# SCH_Nucleo__LCD__v3_2022-11-11.net
KiCad netlist of a schematic drawn in EasyEDA
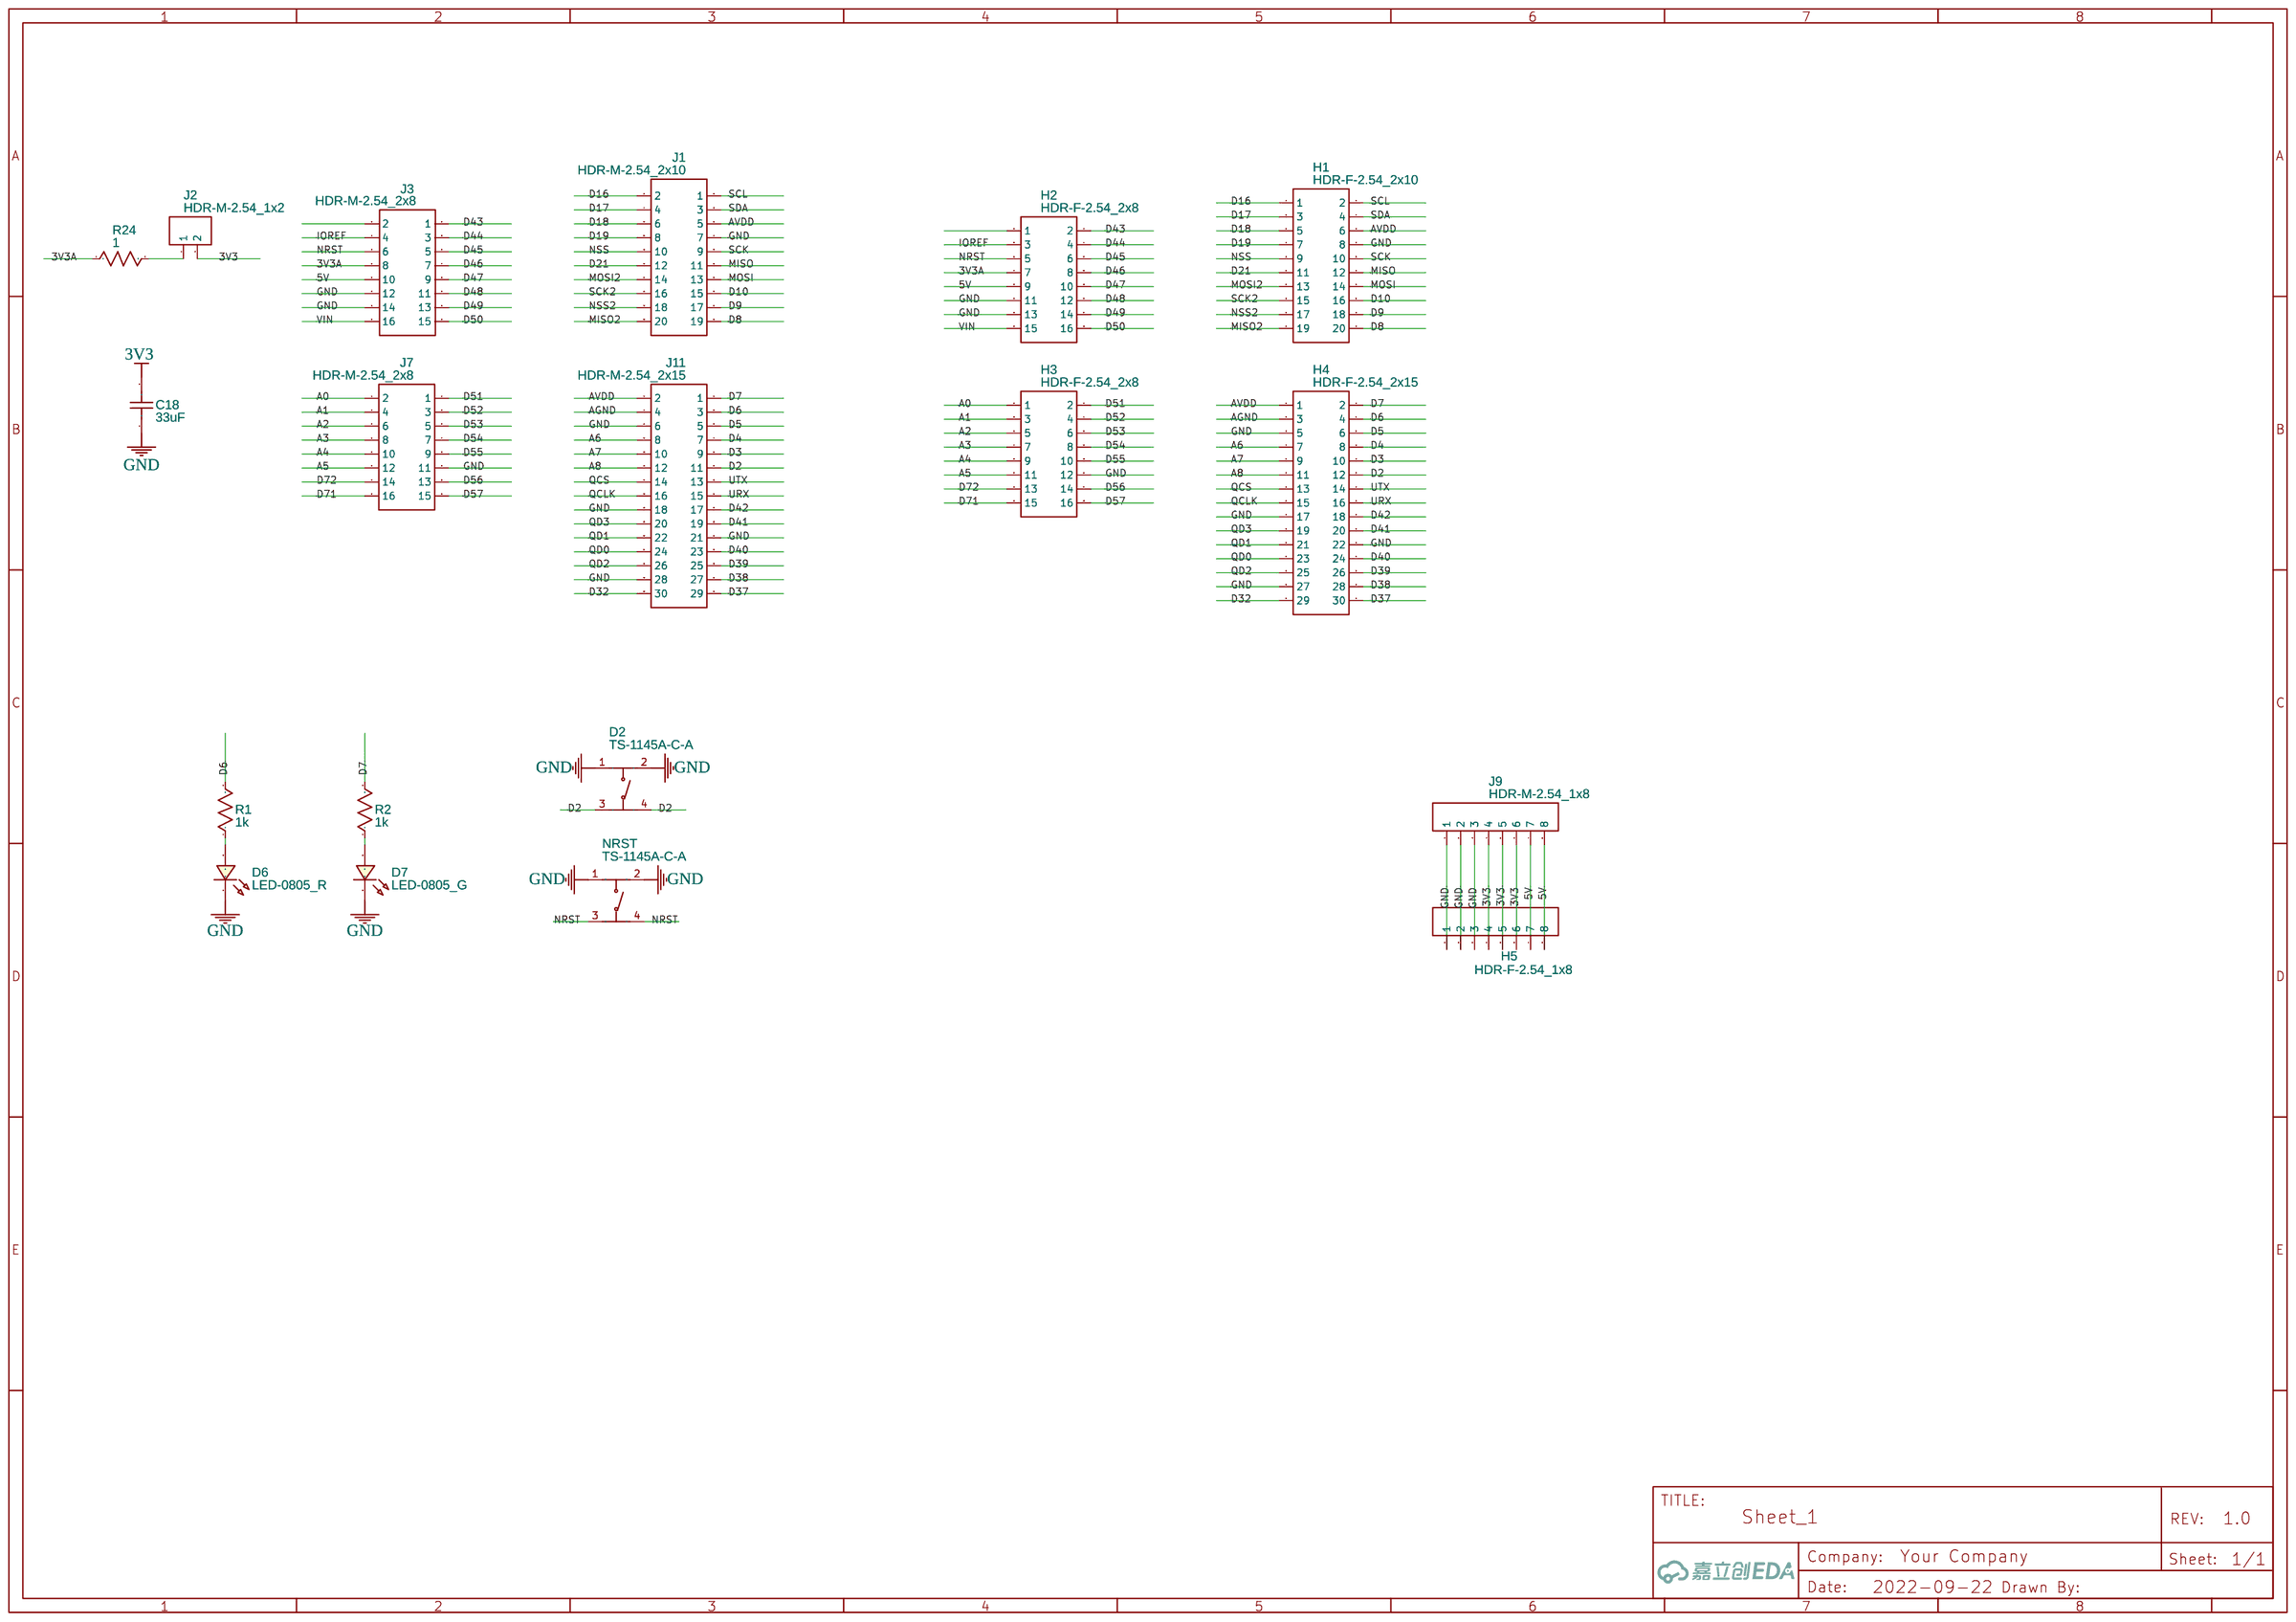
[diagram p0: 连接器]
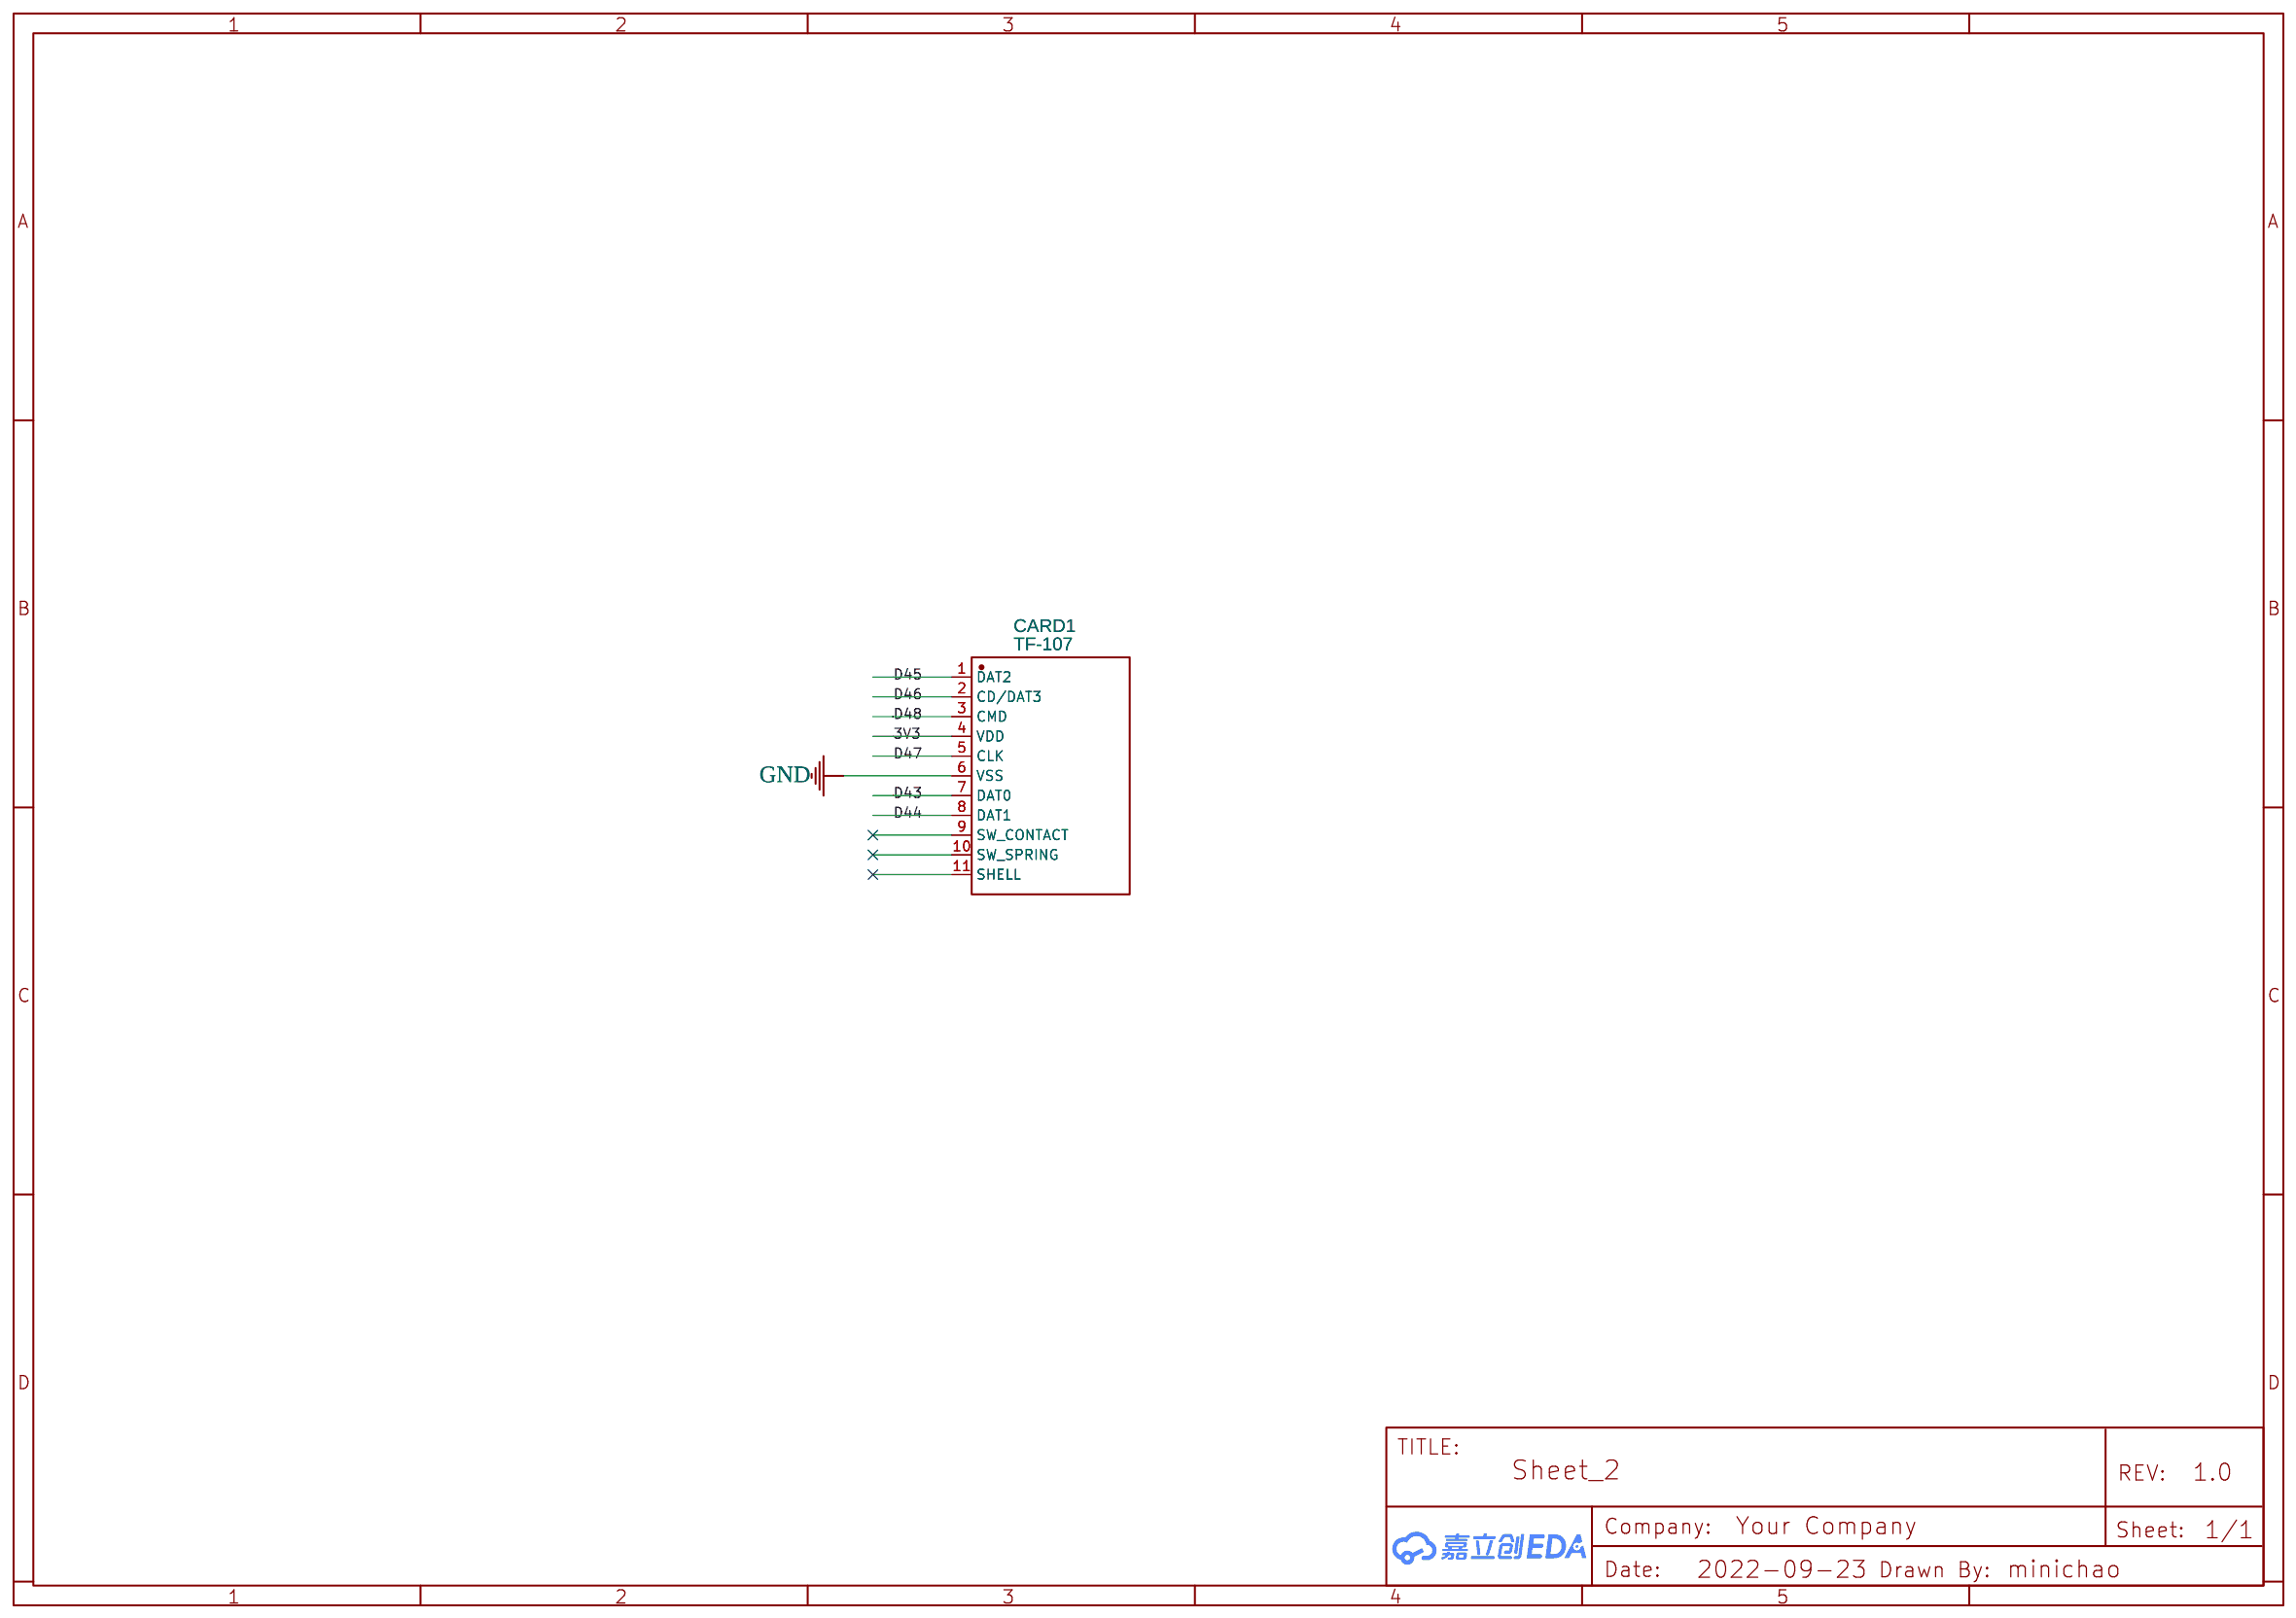
[diagram p1: 存储]
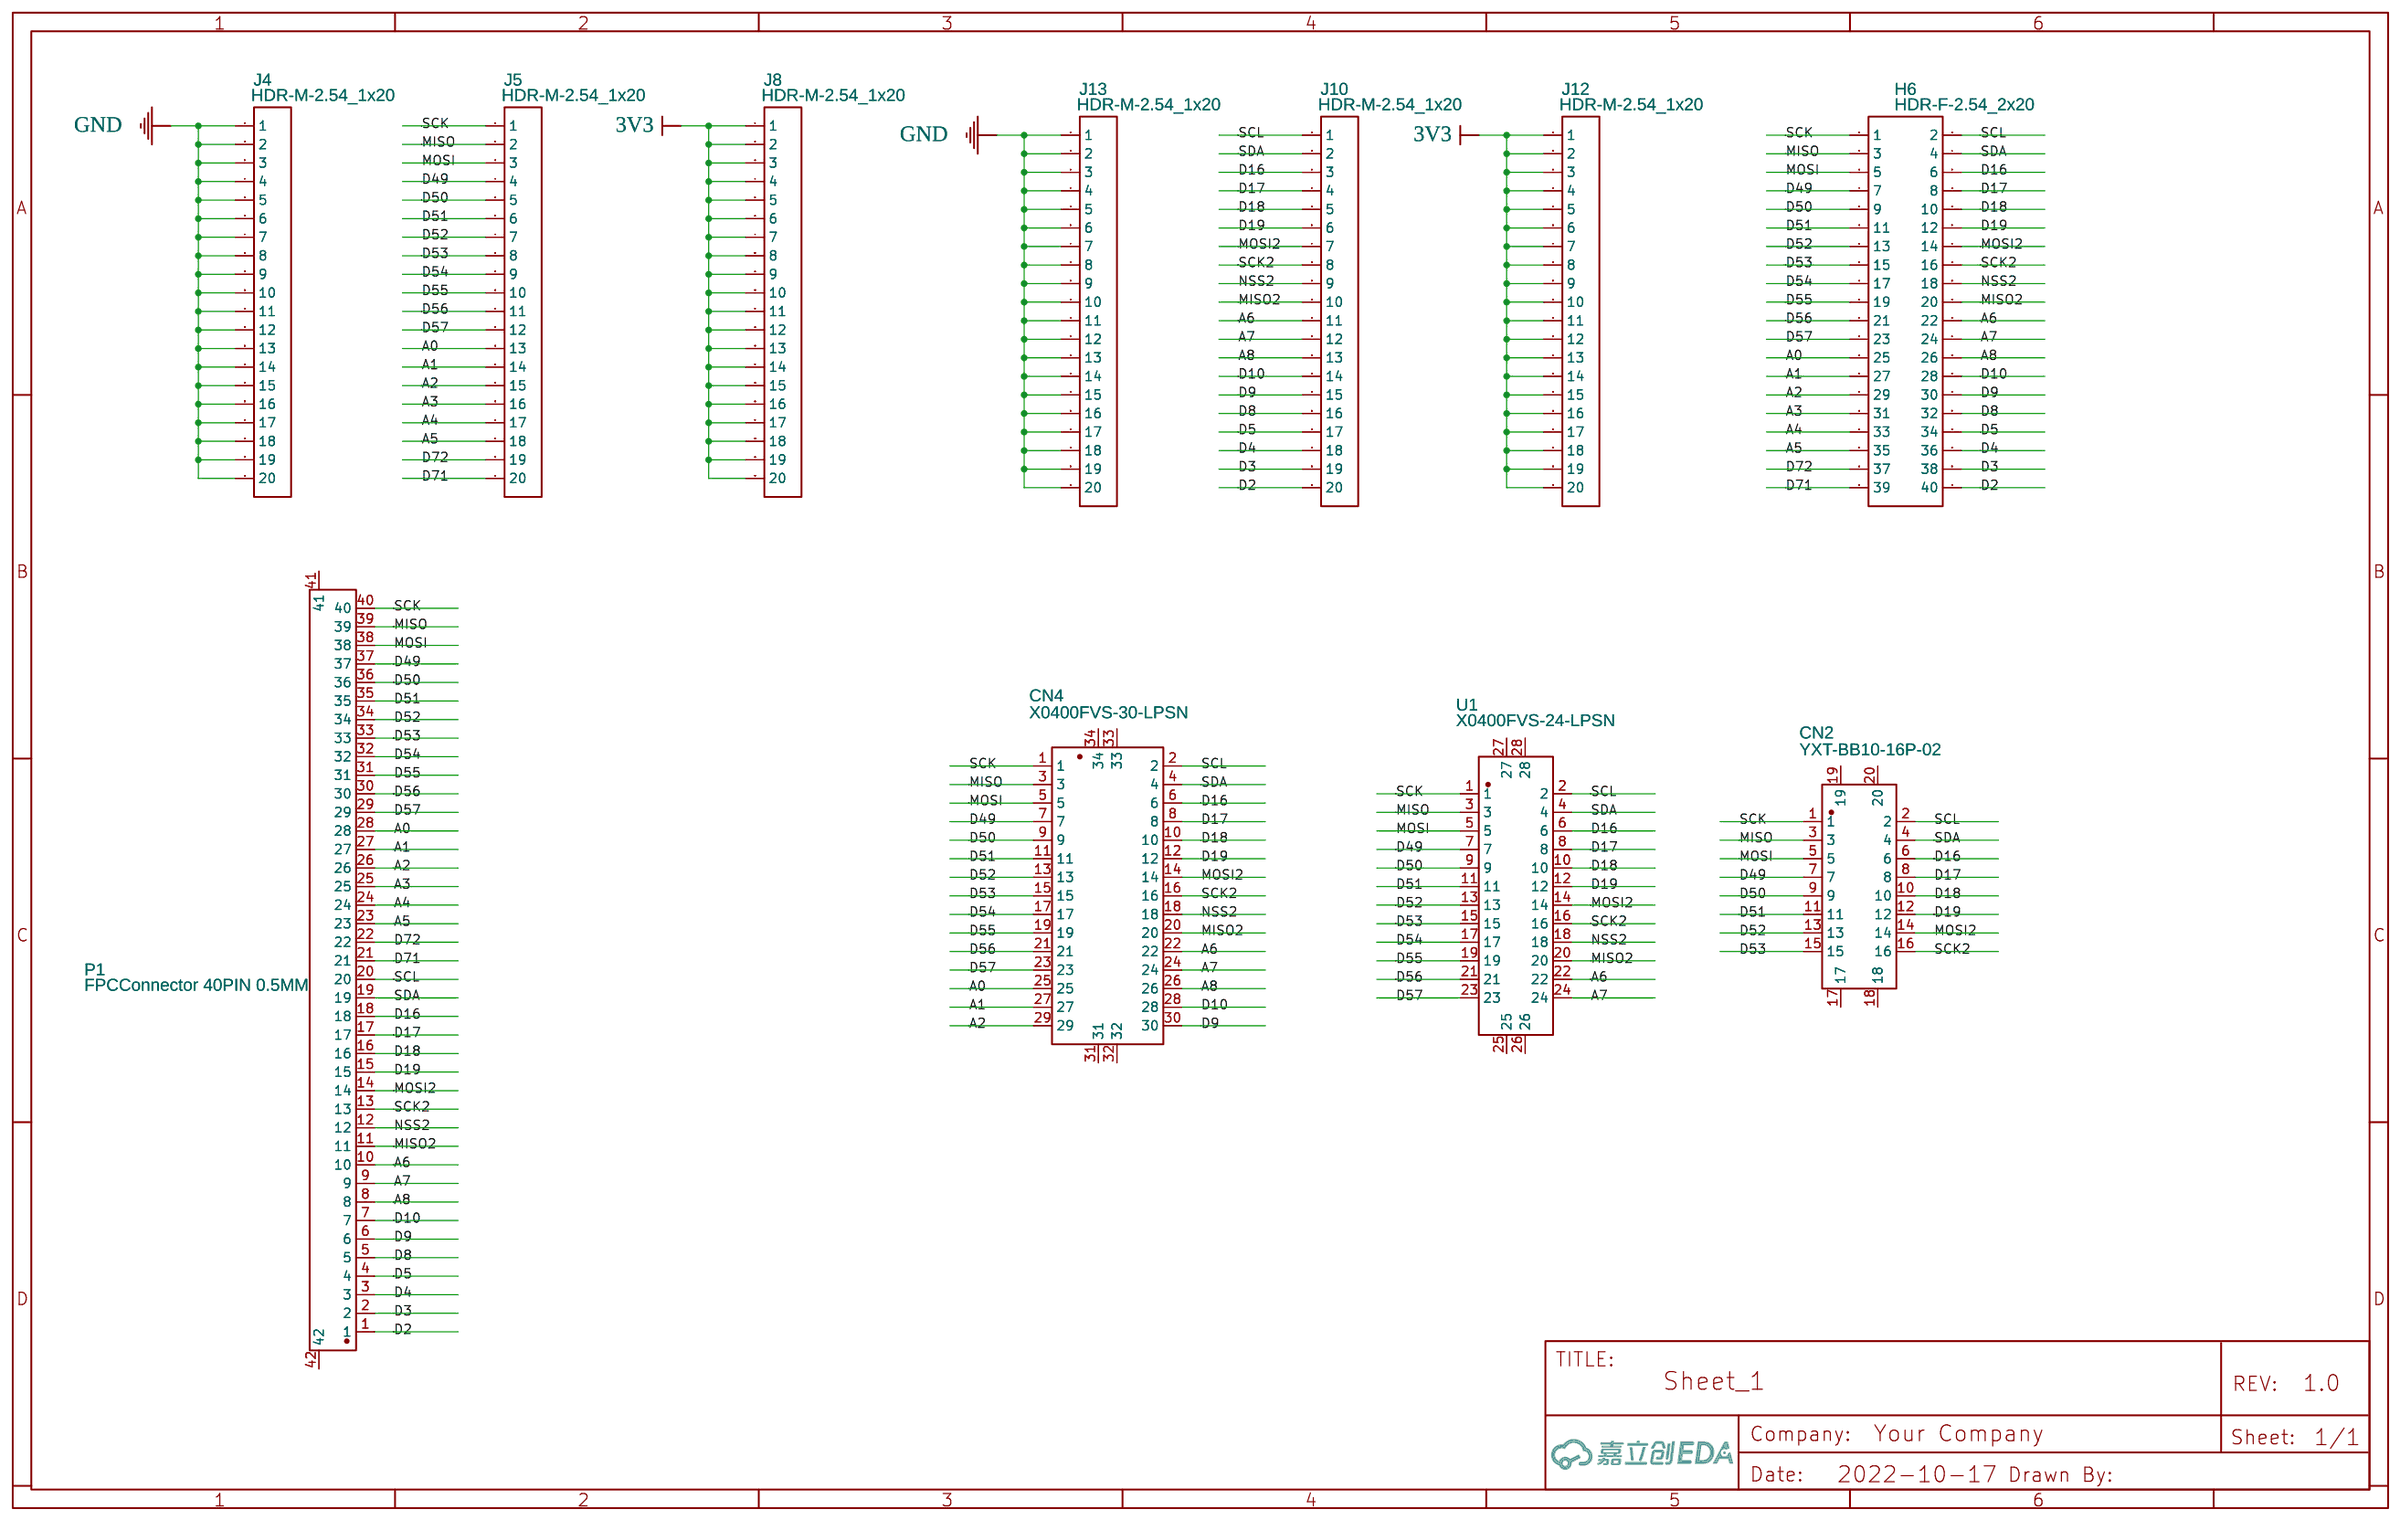
[diagram p2: 显示]

(export (version "E")
  (design (tool "Eeschema 10.0.6"))
  (components
    (comp (ref "C18")
      (value "33uF")
      (fields
        (field (name "BOM_Manufacturer Part") "C3225X5R0J336MT0A0N")
        (field (name "BOM_Supplier Part") "C695362")
      )
      (libsource (lib "") (part "C3225X5R0J336MT0A0N"))
    )
    (comp (ref "D2")
      (value "TS-1145A-C-A")
      (fields (field (name "BOM_Supplier Part") "C318903"))
      (libsource (lib "") (part "TS-1145A-C-A"))
    )
    (comp (ref "D6")
      (value "LED-0805_R")
      (fields
        (field (name "BOM_Manufacturer Part") "17-21SURC/S530-A3/TR8")
        (field (name "BOM_Supplier Part") "C72037")
      )
      (libsource (lib "") (part "LED-0805_R"))
    )
    (comp (ref "D7")
      (value "LED-0805_G")
      (fields (field (name "BOM_Manufacturer Part") "NCD0805G1") (field (name "BOM_Supplier Part") "C84260"))
      (libsource (lib "") (part "LED-0805_G"))
    )
    (comp (ref "H1")
      (value "HDR-F-2.54_2x10")
      (fields (field (name "BOM_Supplier Part") "C30867"))
      (libsource (lib "") (part "HDR-F-2.54_2x10"))
    )
    (comp (ref "H2")
      (value "HDR-F-2.54_2x8")
      (fields (field (name "BOM_Supplier Part") "C30734"))
      (libsource (lib "") (part "HDR-F-2.54_2x8"))
    )
    (comp (ref "H3")
      (value "HDR-F-2.54_2x8")
      (fields (field (name "BOM_Supplier Part") "C30734"))
      (libsource (lib "") (part "HDR-F-2.54_2x8"))
    )
    (comp (ref "H4")
      (value "HDR-F-2.54_2x15")
      (fields (field (name "BOM_Supplier Part") "C169818"))
      (libsource (lib "") (part "HDR-F-2.54_2x15"))
    )
    (comp (ref "H5")
      (value "HDR-F-2.54_1x8")
      (fields (field (name "BOM_Supplier Part") "C225505"))
      (libsource (lib "") (part "HDR-F-2.54_1x8"))
    )
    (comp (ref "J1")
      (value "HDR-M-2.54_2x10")
      (fields (field (name "BOM_Supplier Part") "C124359"))
      (libsource (lib "") (part "HDR-M-2.54_2x10"))
    )
    (comp (ref "J2")
      (value "HDR-M-2.54_1x2")
      (fields (field (name "BOM_Supplier Part") "C124375"))
      (libsource (lib "") (part "HDR-M-2.54_1x2"))
    )
    (comp (ref "J3")
      (value "HDR-M-2.54_2x8")
      (fields (field (name "BOM_Supplier Part") "C68234"))
      (libsource (lib "") (part "HDR-M-2.54_2x8"))
    )
    (comp (ref "J7")
      (value "HDR-M-2.54_2x8")
      (fields (field (name "BOM_Supplier Part") "C68234"))
      (libsource (lib "") (part "HDR-M-2.54_2x8_1"))
    )
    (comp (ref "J9")
      (value "HDR-M-2.54_1x8")
      (fields (field (name "BOM_Supplier Part") "C190820"))
      (libsource (lib "") (part "HDR-M-2.54_1x8"))
    )
    (comp (ref "J11")
      (value "HDR-M-2.54_2x15")
      (fields (field (name "BOM_Supplier Part") "C56496"))
      (libsource (lib "") (part "HDR-M-2.54_2x15"))
    )
    (comp (ref "NRST")
      (value "TS-1145A-C-A")
      (fields (field (name "BOM_Supplier Part") "C318903"))
      (libsource (lib "") (part "TS-1145A-C-A_1"))
    )
    (comp (ref "R1")
      (value "1k")
      (fields
        (field (name "BOM_Manufacturer Part") "TC0525F1001T5E")
        (field (name "BOM_Supplier Part") "C75781")
      )
      (libsource (lib "") (part "R_0805_US"))
    )
    (comp (ref "R2")
      (value "1k")
      (fields
        (field (name "BOM_Manufacturer Part") "TC0525F1001T5E")
        (field (name "BOM_Supplier Part") "C75781")
      )
      (libsource (lib "") (part "R_0805_US"))
    )
    (comp (ref "R24") (value "1") (libsource (lib "") (part "R_0805_US_1")))
    (comp (ref "CARD1")
      (value "TF-107")
      (fields (field (name "BOM_Supplier Part") "C266615"))
      (libsource (lib "") (part "TF-107"))
    )
    (comp (ref "CN2")
      (value "YXT-BB10-16P-02")
      (fields (field (name "BOM_Supplier Part") "C2763972"))
      (libsource (lib "") (part "YXT-BB10-16P-02"))
    )
    (comp (ref "CN4")
      (value "X0400FVS-30-LPSN")
      (fields (field (name "BOM_Supplier Part") "C2880693"))
      (libsource (lib "") (part "X0400FVS-30-LPSN"))
    )
    (comp (ref "H6")
      (value "HDR-F-2.54_2x20")
      (fields (field (name "BOM_Supplier Part") "C50982"))
      (libsource (lib "") (part "HDR-F-2.54_2x20"))
    )
    (comp (ref "J4")
      (value "HDR-M-2.54_1x20")
      (fields (field (name "BOM_Supplier Part") "C50981"))
      (libsource (lib "") (part "HDR-M-2.54_1x20"))
    )
    (comp (ref "J5")
      (value "HDR-M-2.54_1x20")
      (fields (field (name "BOM_Supplier Part") "C50981"))
      (libsource (lib "") (part "HDR-M-2.54_1x20"))
    )
    (comp (ref "J8")
      (value "HDR-M-2.54_1x20")
      (fields (field (name "BOM_Supplier Part") "C50981"))
      (libsource (lib "") (part "HDR-M-2.54_1x20"))
    )
    (comp (ref "J10")
      (value "HDR-M-2.54_1x20")
      (fields (field (name "BOM_Supplier Part") "C50981"))
      (libsource (lib "") (part "HDR-M-2.54_1x20"))
    )
    (comp (ref "J12")
      (value "HDR-M-2.54_1x20")
      (fields (field (name "BOM_Supplier Part") "C50981"))
      (libsource (lib "") (part "HDR-M-2.54_1x20"))
    )
    (comp (ref "J13")
      (value "HDR-M-2.54_1x20")
      (fields (field (name "BOM_Supplier Part") "C50981"))
      (libsource (lib "") (part "HDR-M-2.54_1x20"))
    )
    (comp (ref "P1")
      (value "FPCConnector 40PIN 0.5MM")
      (fields (field (name "BOM_Manufacturer Part") "0.5-40P翻盖") (field (name "BOM_Supplier Part") "C9160"))
      (libsource (lib "") (part "FPCConnector 40PIN 0.5MM"))
    )
    (comp (ref "U1")
      (value "X0400FVS-24-LPSN")
      (fields (field (name "BOM_Supplier Part") "C2880692"))
      (libsource (lib "") (part "X0400FVS-24-LPSN"))
    )
  )
  (nets
    (net (code "1") (name "3V3") (class "Default")
      (node (ref "C18") (pin "2") (pinfunction "2_2") (pintype "unspecified"))
      (node (ref "CARD1") (pin "4") (pinfunction "VDD_4") (pintype "unspecified"))
      (node (ref "H5") (pin "4") (pinfunction "4_4") (pintype "unspecified"))
      (node (ref "H5") (pin "5") (pinfunction "5_5") (pintype "unspecified"))
      (node (ref "H5") (pin "6") (pinfunction "6_6") (pintype "unspecified"))
      (node (ref "J12") (pin "1") (pinfunction "1_1") (pintype "unspecified"))
      (node (ref "J12") (pin "10") (pinfunction "10_10") (pintype "unspecified"))
      (node (ref "J12") (pin "11") (pinfunction "11_11") (pintype "unspecified"))
      (node (ref "J12") (pin "12") (pinfunction "12_12") (pintype "unspecified"))
      (node (ref "J12") (pin "13") (pinfunction "13_13") (pintype "unspecified"))
      (node (ref "J12") (pin "14") (pinfunction "14_14") (pintype "unspecified"))
      (node (ref "J12") (pin "15") (pinfunction "15_15") (pintype "unspecified"))
      (node (ref "J12") (pin "16") (pinfunction "16_16") (pintype "unspecified"))
      (node (ref "J12") (pin "17") (pinfunction "17_17") (pintype "unspecified"))
      (node (ref "J12") (pin "18") (pinfunction "18_18") (pintype "unspecified"))
      (node (ref "J12") (pin "19") (pinfunction "19_19") (pintype "unspecified"))
      (node (ref "J12") (pin "2") (pinfunction "2_2") (pintype "unspecified"))
      (node (ref "J12") (pin "20") (pinfunction "20_20") (pintype "unspecified"))
      (node (ref "J12") (pin "3") (pinfunction "3_3") (pintype "unspecified"))
      (node (ref "J12") (pin "4") (pinfunction "4_4") (pintype "unspecified"))
      (node (ref "J12") (pin "5") (pinfunction "5_5") (pintype "unspecified"))
      (node (ref "J12") (pin "6") (pinfunction "6_6") (pintype "unspecified"))
      (node (ref "J12") (pin "7") (pinfunction "7_7") (pintype "unspecified"))
      (node (ref "J12") (pin "8") (pinfunction "8_8") (pintype "unspecified"))
      (node (ref "J12") (pin "9") (pinfunction "9_9") (pintype "unspecified"))
      (node (ref "J2") (pin "2") (pinfunction "2_2") (pintype "unspecified"))
      (node (ref "J8") (pin "1") (pinfunction "1_1") (pintype "unspecified"))
      (node (ref "J8") (pin "10") (pinfunction "10_10") (pintype "unspecified"))
      (node (ref "J8") (pin "11") (pinfunction "11_11") (pintype "unspecified"))
      (node (ref "J8") (pin "12") (pinfunction "12_12") (pintype "unspecified"))
      (node (ref "J8") (pin "13") (pinfunction "13_13") (pintype "unspecified"))
      (node (ref "J8") (pin "14") (pinfunction "14_14") (pintype "unspecified"))
      (node (ref "J8") (pin "15") (pinfunction "15_15") (pintype "unspecified"))
      (node (ref "J8") (pin "16") (pinfunction "16_16") (pintype "unspecified"))
      (node (ref "J8") (pin "17") (pinfunction "17_17") (pintype "unspecified"))
      (node (ref "J8") (pin "18") (pinfunction "18_18") (pintype "unspecified"))
      (node (ref "J8") (pin "19") (pinfunction "19_19") (pintype "unspecified"))
      (node (ref "J8") (pin "2") (pinfunction "2_2") (pintype "unspecified"))
      (node (ref "J8") (pin "20") (pinfunction "20_20") (pintype "unspecified"))
      (node (ref "J8") (pin "3") (pinfunction "3_3") (pintype "unspecified"))
      (node (ref "J8") (pin "4") (pinfunction "4_4") (pintype "unspecified"))
      (node (ref "J8") (pin "5") (pinfunction "5_5") (pintype "unspecified"))
      (node (ref "J8") (pin "6") (pinfunction "6_6") (pintype "unspecified"))
      (node (ref "J8") (pin "7") (pinfunction "7_7") (pintype "unspecified"))
      (node (ref "J8") (pin "8") (pinfunction "8_8") (pintype "unspecified"))
      (node (ref "J8") (pin "9") (pinfunction "9_9") (pintype "unspecified"))
      (node (ref "J9") (pin "4") (pinfunction "4_4") (pintype "unspecified"))
      (node (ref "J9") (pin "5") (pinfunction "5_5") (pintype "unspecified"))
      (node (ref "J9") (pin "6") (pinfunction "6_6") (pintype "unspecified"))
    )
    (net (code "2") (name "3V3A") (class "Default")
      (node (ref "H2") (pin "7") (pinfunction "7_7") (pintype "input"))
      (node (ref "J3") (pin "8") (pinfunction "8_8") (pintype "input"))
      (node (ref "R24") (pin "1") (pinfunction "1_1") (pintype "unspecified"))
    )
    (net (code "3") (name "5V") (class "Default")
      (node (ref "H2") (pin "9") (pinfunction "9_9") (pintype "input"))
      (node (ref "H5") (pin "7") (pinfunction "7_7") (pintype "unspecified"))
      (node (ref "H5") (pin "8") (pinfunction "8_8") (pintype "unspecified"))
      (node (ref "J3") (pin "10") (pinfunction "10_10") (pintype "input"))
      (node (ref "J9") (pin "7") (pinfunction "7_7") (pintype "unspecified"))
      (node (ref "J9") (pin "8") (pinfunction "8_8") (pintype "unspecified"))
    )
    (net (code "4") (name "A0") (class "Default")
      (node (ref "CN4") (pin "25") (pinfunction "25_25") (pintype "unspecified"))
      (node (ref "H3") (pin "1") (pinfunction "1_1") (pintype "input"))
      (node (ref "H6") (pin "25") (pinfunction "25_25") (pintype "input"))
      (node (ref "J5") (pin "13") (pinfunction "13_13") (pintype "unspecified"))
      (node (ref "J7") (pin "2") (pinfunction "2_2") (pintype "input"))
      (node (ref "P1") (pin "28") (pinfunction "28_28") (pintype "unspecified"))
    )
    (net (code "5") (name "A1") (class "Default")
      (node (ref "CN4") (pin "27") (pinfunction "27_27") (pintype "unspecified"))
      (node (ref "H3") (pin "3") (pinfunction "3_3") (pintype "input"))
      (node (ref "H6") (pin "27") (pinfunction "27_27") (pintype "input"))
      (node (ref "J5") (pin "14") (pinfunction "14_14") (pintype "unspecified"))
      (node (ref "J7") (pin "4") (pinfunction "4_4") (pintype "input"))
      (node (ref "P1") (pin "27") (pinfunction "27_27") (pintype "unspecified"))
    )
    (net (code "6") (name "A2") (class "Default")
      (node (ref "CN4") (pin "29") (pinfunction "29_29") (pintype "unspecified"))
      (node (ref "H3") (pin "5") (pinfunction "5_5") (pintype "input"))
      (node (ref "H6") (pin "29") (pinfunction "29_29") (pintype "input"))
      (node (ref "J5") (pin "15") (pinfunction "15_15") (pintype "unspecified"))
      (node (ref "J7") (pin "6") (pinfunction "6_6") (pintype "input"))
      (node (ref "P1") (pin "26") (pinfunction "26_26") (pintype "unspecified"))
    )
    (net (code "7") (name "A3") (class "Default")
      (node (ref "H3") (pin "7") (pinfunction "7_7") (pintype "input"))
      (node (ref "H6") (pin "31") (pinfunction "31_31") (pintype "input"))
      (node (ref "J5") (pin "16") (pinfunction "16_16") (pintype "unspecified"))
      (node (ref "J7") (pin "8") (pinfunction "8_8") (pintype "input"))
      (node (ref "P1") (pin "25") (pinfunction "25_25") (pintype "unspecified"))
    )
    (net (code "8") (name "A4") (class "Default")
      (node (ref "H3") (pin "9") (pinfunction "9_9") (pintype "input"))
      (node (ref "H6") (pin "33") (pinfunction "33_33") (pintype "input"))
      (node (ref "J5") (pin "17") (pinfunction "17_17") (pintype "unspecified"))
      (node (ref "J7") (pin "10") (pinfunction "10_10") (pintype "input"))
      (node (ref "P1") (pin "24") (pinfunction "24_24") (pintype "unspecified"))
    )
    (net (code "9") (name "A5") (class "Default")
      (node (ref "H3") (pin "11") (pinfunction "11_11") (pintype "input"))
      (node (ref "H6") (pin "35") (pinfunction "35_35") (pintype "input"))
      (node (ref "J5") (pin "18") (pinfunction "18_18") (pintype "unspecified"))
      (node (ref "J7") (pin "12") (pinfunction "12_12") (pintype "input"))
      (node (ref "P1") (pin "23") (pinfunction "23_23") (pintype "unspecified"))
    )
    (net (code "10") (name "A6") (class "Default")
      (node (ref "CN4") (pin "22") (pinfunction "22_22") (pintype "unspecified"))
      (node (ref "H4") (pin "7") (pinfunction "7_7") (pintype "input"))
      (node (ref "H6") (pin "22") (pinfunction "22_22") (pintype "input"))
      (node (ref "J10") (pin "11") (pinfunction "11_11") (pintype "unspecified"))
      (node (ref "J11") (pin "8") (pinfunction "8_8") (pintype "input"))
      (node (ref "P1") (pin "10") (pinfunction "10_10") (pintype "unspecified"))
      (node (ref "U1") (pin "22") (pinfunction "22_22") (pintype "unspecified"))
    )
    (net (code "11") (name "A7") (class "Default")
      (node (ref "CN4") (pin "24") (pinfunction "24_24") (pintype "unspecified"))
      (node (ref "H4") (pin "9") (pinfunction "9_9") (pintype "input"))
      (node (ref "H6") (pin "24") (pinfunction "24_24") (pintype "input"))
      (node (ref "J10") (pin "12") (pinfunction "12_12") (pintype "unspecified"))
      (node (ref "J11") (pin "10") (pinfunction "10_10") (pintype "input"))
      (node (ref "P1") (pin "9") (pinfunction "9_9") (pintype "unspecified"))
      (node (ref "U1") (pin "24") (pinfunction "24_24") (pintype "unspecified"))
    )
    (net (code "12") (name "A8") (class "Default")
      (node (ref "CN4") (pin "26") (pinfunction "26_26") (pintype "unspecified"))
      (node (ref "H4") (pin "11") (pinfunction "11_11") (pintype "input"))
      (node (ref "H6") (pin "26") (pinfunction "26_26") (pintype "input"))
      (node (ref "J10") (pin "13") (pinfunction "13_13") (pintype "unspecified"))
      (node (ref "J11") (pin "12") (pinfunction "12_12") (pintype "input"))
      (node (ref "P1") (pin "8") (pinfunction "8_8") (pintype "unspecified"))
    )
    (net (code "13") (name "AGND") (class "Default")
      (node (ref "H4") (pin "3") (pinfunction "3_3") (pintype "input"))
      (node (ref "J11") (pin "4") (pinfunction "4_4") (pintype "input"))
    )
    (net (code "14") (name "AVDD") (class "Default")
      (node (ref "H1") (pin "6") (pinfunction "6_6") (pintype "input"))
      (node (ref "H4") (pin "1") (pinfunction "1_1") (pintype "input"))
      (node (ref "J1") (pin "5") (pinfunction "5_5") (pintype "unspecified"))
      (node (ref "J11") (pin "2") (pinfunction "2_2") (pintype "input"))
    )
    (net (code "15") (name "D2") (class "Default")
      (node (ref "D2") (pin "3") (pinfunction "3_3") (pintype "unspecified"))
      (node (ref "D2") (pin "4") (pinfunction "4_4") (pintype "unspecified"))
      (node (ref "H4") (pin "12") (pinfunction "12_12") (pintype "input"))
      (node (ref "H6") (pin "40") (pinfunction "40_40") (pintype "input"))
      (node (ref "J10") (pin "20") (pinfunction "20_20") (pintype "unspecified"))
      (node (ref "J11") (pin "11") (pinfunction "11_11") (pintype "input"))
      (node (ref "P1") (pin "1") (pinfunction "1_1") (pintype "unspecified"))
    )
    (net (code "16") (name "D3") (class "Default")
      (node (ref "H4") (pin "10") (pinfunction "10_10") (pintype "input"))
      (node (ref "H6") (pin "38") (pinfunction "38_38") (pintype "input"))
      (node (ref "J10") (pin "19") (pinfunction "19_19") (pintype "unspecified"))
      (node (ref "J11") (pin "9") (pinfunction "9_9") (pintype "input"))
      (node (ref "P1") (pin "2") (pinfunction "2_2") (pintype "unspecified"))
    )
    (net (code "17") (name "D4") (class "Default")
      (node (ref "H4") (pin "8") (pinfunction "8_8") (pintype "input"))
      (node (ref "H6") (pin "36") (pinfunction "36_36") (pintype "input"))
      (node (ref "J10") (pin "18") (pinfunction "18_18") (pintype "unspecified"))
      (node (ref "J11") (pin "7") (pinfunction "7_7") (pintype "input"))
      (node (ref "P1") (pin "3") (pinfunction "3_3") (pintype "unspecified"))
    )
    (net (code "18") (name "D5") (class "Default")
      (node (ref "H4") (pin "6") (pinfunction "6_6") (pintype "input"))
      (node (ref "H6") (pin "34") (pinfunction "34_34") (pintype "input"))
      (node (ref "J10") (pin "17") (pinfunction "17_17") (pintype "unspecified"))
      (node (ref "J11") (pin "5") (pinfunction "5_5") (pintype "input"))
      (node (ref "P1") (pin "4") (pinfunction "4_4") (pintype "unspecified"))
    )
    (net (code "19") (name "D6") (class "Default")
      (node (ref "H4") (pin "4") (pinfunction "4_4") (pintype "input"))
      (node (ref "J11") (pin "3") (pinfunction "3_3") (pintype "input"))
      (node (ref "R1") (pin "2") (pinfunction "2_2") (pintype "unspecified"))
    )
    (net (code "20") (name "D7") (class "Default")
      (node (ref "H4") (pin "2") (pinfunction "2_2") (pintype "input"))
      (node (ref "J11") (pin "1") (pinfunction "1_1") (pintype "input"))
      (node (ref "R2") (pin "2") (pinfunction "2_2") (pintype "unspecified"))
    )
    (net (code "21") (name "D8") (class "Default")
      (node (ref "H1") (pin "20") (pinfunction "20_20") (pintype "input"))
      (node (ref "H6") (pin "32") (pinfunction "32_32") (pintype "input"))
      (node (ref "J1") (pin "19") (pinfunction "19_19") (pintype "unspecified"))
      (node (ref "J10") (pin "16") (pinfunction "16_16") (pintype "unspecified"))
      (node (ref "P1") (pin "5") (pinfunction "5_5") (pintype "unspecified"))
    )
    (net (code "22") (name "D9") (class "Default")
      (node (ref "CN4") (pin "30") (pinfunction "30_30") (pintype "unspecified"))
      (node (ref "H1") (pin "18") (pinfunction "18_18") (pintype "input"))
      (node (ref "H6") (pin "30") (pinfunction "30_30") (pintype "input"))
      (node (ref "J1") (pin "17") (pinfunction "17_17") (pintype "unspecified"))
      (node (ref "J10") (pin "15") (pinfunction "15_15") (pintype "unspecified"))
      (node (ref "P1") (pin "6") (pinfunction "6_6") (pintype "unspecified"))
    )
    (net (code "23") (name "D10") (class "Default")
      (node (ref "CN4") (pin "28") (pinfunction "28_28") (pintype "unspecified"))
      (node (ref "H1") (pin "16") (pinfunction "16_16") (pintype "input"))
      (node (ref "H6") (pin "28") (pinfunction "28_28") (pintype "input"))
      (node (ref "J1") (pin "15") (pinfunction "15_15") (pintype "unspecified"))
      (node (ref "J10") (pin "14") (pinfunction "14_14") (pintype "unspecified"))
      (node (ref "P1") (pin "7") (pinfunction "7_7") (pintype "unspecified"))
    )
    (net (code "24") (name "D16") (class "Default")
      (node (ref "CN2") (pin "6") (pinfunction "6_6") (pintype "unspecified"))
      (node (ref "CN4") (pin "6") (pinfunction "6_6") (pintype "unspecified"))
      (node (ref "H1") (pin "1") (pinfunction "1_1") (pintype "input"))
      (node (ref "H6") (pin "6") (pinfunction "6_6") (pintype "input"))
      (node (ref "J1") (pin "2") (pinfunction "2_2") (pintype "unspecified"))
      (node (ref "J10") (pin "3") (pinfunction "3_3") (pintype "unspecified"))
      (node (ref "P1") (pin "18") (pinfunction "18_18") (pintype "unspecified"))
      (node (ref "U1") (pin "6") (pinfunction "6_6") (pintype "unspecified"))
    )
    (net (code "25") (name "D17") (class "Default")
      (node (ref "CN2") (pin "8") (pinfunction "8_8") (pintype "unspecified"))
      (node (ref "CN4") (pin "8") (pinfunction "8_8") (pintype "unspecified"))
      (node (ref "H1") (pin "3") (pinfunction "3_3") (pintype "input"))
      (node (ref "H6") (pin "8") (pinfunction "8_8") (pintype "input"))
      (node (ref "J1") (pin "4") (pinfunction "4_4") (pintype "unspecified"))
      (node (ref "J10") (pin "4") (pinfunction "4_4") (pintype "unspecified"))
      (node (ref "P1") (pin "17") (pinfunction "17_17") (pintype "unspecified"))
      (node (ref "U1") (pin "8") (pinfunction "8_8") (pintype "unspecified"))
    )
    (net (code "26") (name "D18") (class "Default")
      (node (ref "CN2") (pin "10") (pinfunction "10_10") (pintype "unspecified"))
      (node (ref "CN4") (pin "10") (pinfunction "10_10") (pintype "unspecified"))
      (node (ref "H1") (pin "5") (pinfunction "5_5") (pintype "input"))
      (node (ref "H6") (pin "10") (pinfunction "10_10") (pintype "input"))
      (node (ref "J1") (pin "6") (pinfunction "6_6") (pintype "unspecified"))
      (node (ref "J10") (pin "5") (pinfunction "5_5") (pintype "unspecified"))
      (node (ref "P1") (pin "16") (pinfunction "16_16") (pintype "unspecified"))
      (node (ref "U1") (pin "10") (pinfunction "10_10") (pintype "unspecified"))
    )
    (net (code "27") (name "D19") (class "Default")
      (node (ref "CN2") (pin "12") (pinfunction "12_12") (pintype "unspecified"))
      (node (ref "CN4") (pin "12") (pinfunction "12_12") (pintype "unspecified"))
      (node (ref "H1") (pin "7") (pinfunction "7_7") (pintype "input"))
      (node (ref "H6") (pin "12") (pinfunction "12_12") (pintype "input"))
      (node (ref "J1") (pin "8") (pinfunction "8_8") (pintype "unspecified"))
      (node (ref "J10") (pin "6") (pinfunction "6_6") (pintype "unspecified"))
      (node (ref "P1") (pin "15") (pinfunction "15_15") (pintype "unspecified"))
      (node (ref "U1") (pin "12") (pinfunction "12_12") (pintype "unspecified"))
    )
    (net (code "28") (name "D21") (class "Default")
      (node (ref "H1") (pin "11") (pinfunction "11_11") (pintype "input"))
      (node (ref "J1") (pin "12") (pinfunction "12_12") (pintype "unspecified"))
    )
    (net (code "29") (name "D32") (class "Default")
      (node (ref "H4") (pin "29") (pinfunction "29_29") (pintype "input"))
      (node (ref "J11") (pin "30") (pinfunction "30_30") (pintype "input"))
    )
    (net (code "30") (name "D37") (class "Default")
      (node (ref "H4") (pin "30") (pinfunction "30_30") (pintype "input"))
      (node (ref "J11") (pin "29") (pinfunction "29_29") (pintype "input"))
    )
    (net (code "31") (name "D38") (class "Default")
      (node (ref "H4") (pin "28") (pinfunction "28_28") (pintype "input"))
      (node (ref "J11") (pin "27") (pinfunction "27_27") (pintype "input"))
    )
    (net (code "32") (name "D39") (class "Default")
      (node (ref "H4") (pin "26") (pinfunction "26_26") (pintype "input"))
      (node (ref "J11") (pin "25") (pinfunction "25_25") (pintype "input"))
    )
    (net (code "33") (name "D40") (class "Default")
      (node (ref "H4") (pin "24") (pinfunction "24_24") (pintype "input"))
      (node (ref "J11") (pin "23") (pinfunction "23_23") (pintype "input"))
    )
    (net (code "34") (name "D41") (class "Default")
      (node (ref "H4") (pin "20") (pinfunction "20_20") (pintype "input"))
      (node (ref "J11") (pin "19") (pinfunction "19_19") (pintype "input"))
    )
    (net (code "35") (name "D42") (class "Default")
      (node (ref "H4") (pin "18") (pinfunction "18_18") (pintype "input"))
      (node (ref "J11") (pin "17") (pinfunction "17_17") (pintype "input"))
    )
    (net (code "36") (name "D43") (class "Default")
      (node (ref "CARD1") (pin "7") (pinfunction "DAT0_7") (pintype "unspecified"))
      (node (ref "H2") (pin "2") (pinfunction "2_2") (pintype "input"))
      (node (ref "J3") (pin "1") (pinfunction "1_1") (pintype "input"))
    )
    (net (code "37") (name "D44") (class "Default")
      (node (ref "CARD1") (pin "8") (pinfunction "DAT1_8") (pintype "unspecified"))
      (node (ref "H2") (pin "4") (pinfunction "4_4") (pintype "input"))
      (node (ref "J3") (pin "3") (pinfunction "3_3") (pintype "input"))
    )
    (net (code "38") (name "D45") (class "Default")
      (node (ref "CARD1") (pin "1") (pinfunction "DAT2_1") (pintype "unspecified"))
      (node (ref "H2") (pin "6") (pinfunction "6_6") (pintype "input"))
      (node (ref "J3") (pin "5") (pinfunction "5_5") (pintype "input"))
    )
    (net (code "39") (name "D46") (class "Default")
      (node (ref "CARD1") (pin "2") (pinfunction "CD/DAT3_2") (pintype "unspecified"))
      (node (ref "H2") (pin "8") (pinfunction "8_8") (pintype "input"))
      (node (ref "J3") (pin "7") (pinfunction "7_7") (pintype "input"))
    )
    (net (code "40") (name "D47") (class "Default")
      (node (ref "CARD1") (pin "5") (pinfunction "CLK_5") (pintype "unspecified"))
      (node (ref "H2") (pin "10") (pinfunction "10_10") (pintype "input"))
      (node (ref "J3") (pin "9") (pinfunction "9_9") (pintype "input"))
    )
    (net (code "41") (name "D48") (class "Default")
      (node (ref "CARD1") (pin "3") (pinfunction "CMD_3") (pintype "unspecified"))
      (node (ref "H2") (pin "12") (pinfunction "12_12") (pintype "input"))
      (node (ref "J3") (pin "11") (pinfunction "11_11") (pintype "input"))
    )
    (net (code "42") (name "D49") (class "Default")
      (node (ref "CN2") (pin "7") (pinfunction "7_7") (pintype "unspecified"))
      (node (ref "CN4") (pin "7") (pinfunction "7_7") (pintype "unspecified"))
      (node (ref "H2") (pin "14") (pinfunction "14_14") (pintype "input"))
      (node (ref "H6") (pin "7") (pinfunction "7_7") (pintype "input"))
      (node (ref "J3") (pin "13") (pinfunction "13_13") (pintype "input"))
      (node (ref "J5") (pin "4") (pinfunction "4_4") (pintype "unspecified"))
      (node (ref "P1") (pin "37") (pinfunction "37_37") (pintype "unspecified"))
      (node (ref "U1") (pin "7") (pinfunction "7_7") (pintype "unspecified"))
    )
    (net (code "43") (name "D50") (class "Default")
      (node (ref "CN2") (pin "9") (pinfunction "9_9") (pintype "unspecified"))
      (node (ref "CN4") (pin "9") (pinfunction "9_9") (pintype "unspecified"))
      (node (ref "H2") (pin "16") (pinfunction "16_16") (pintype "input"))
      (node (ref "H6") (pin "9") (pinfunction "9_9") (pintype "input"))
      (node (ref "J3") (pin "15") (pinfunction "15_15") (pintype "input"))
      (node (ref "J5") (pin "5") (pinfunction "5_5") (pintype "unspecified"))
      (node (ref "P1") (pin "36") (pinfunction "36_36") (pintype "unspecified"))
      (node (ref "U1") (pin "9") (pinfunction "9_9") (pintype "unspecified"))
    )
    (net (code "44") (name "D51") (class "Default")
      (node (ref "CN2") (pin "11") (pinfunction "11_11") (pintype "unspecified"))
      (node (ref "CN4") (pin "11") (pinfunction "11_11") (pintype "unspecified"))
      (node (ref "H3") (pin "2") (pinfunction "2_2") (pintype "input"))
      (node (ref "H6") (pin "11") (pinfunction "11_11") (pintype "input"))
      (node (ref "J5") (pin "6") (pinfunction "6_6") (pintype "unspecified"))
      (node (ref "J7") (pin "1") (pinfunction "1_1") (pintype "input"))
      (node (ref "P1") (pin "35") (pinfunction "35_35") (pintype "unspecified"))
      (node (ref "U1") (pin "11") (pinfunction "11_11") (pintype "unspecified"))
    )
    (net (code "45") (name "D52") (class "Default")
      (node (ref "CN2") (pin "13") (pinfunction "13_13") (pintype "unspecified"))
      (node (ref "CN4") (pin "13") (pinfunction "13_13") (pintype "unspecified"))
      (node (ref "H3") (pin "4") (pinfunction "4_4") (pintype "input"))
      (node (ref "H6") (pin "13") (pinfunction "13_13") (pintype "input"))
      (node (ref "J5") (pin "7") (pinfunction "7_7") (pintype "unspecified"))
      (node (ref "J7") (pin "3") (pinfunction "3_3") (pintype "input"))
      (node (ref "P1") (pin "34") (pinfunction "34_34") (pintype "unspecified"))
      (node (ref "U1") (pin "13") (pinfunction "13_13") (pintype "unspecified"))
    )
    (net (code "46") (name "D53") (class "Default")
      (node (ref "CN2") (pin "15") (pinfunction "15_15") (pintype "unspecified"))
      (node (ref "CN4") (pin "15") (pinfunction "15_15") (pintype "unspecified"))
      (node (ref "H3") (pin "6") (pinfunction "6_6") (pintype "input"))
      (node (ref "H6") (pin "15") (pinfunction "15_15") (pintype "input"))
      (node (ref "J5") (pin "8") (pinfunction "8_8") (pintype "unspecified"))
      (node (ref "J7") (pin "5") (pinfunction "5_5") (pintype "input"))
      (node (ref "P1") (pin "33") (pinfunction "33_33") (pintype "unspecified"))
      (node (ref "U1") (pin "15") (pinfunction "15_15") (pintype "unspecified"))
    )
    (net (code "47") (name "D54") (class "Default")
      (node (ref "CN4") (pin "17") (pinfunction "17_17") (pintype "unspecified"))
      (node (ref "H3") (pin "8") (pinfunction "8_8") (pintype "input"))
      (node (ref "H6") (pin "17") (pinfunction "17_17") (pintype "input"))
      (node (ref "J5") (pin "9") (pinfunction "9_9") (pintype "unspecified"))
      (node (ref "J7") (pin "7") (pinfunction "7_7") (pintype "input"))
      (node (ref "P1") (pin "32") (pinfunction "32_32") (pintype "unspecified"))
      (node (ref "U1") (pin "17") (pinfunction "17_17") (pintype "unspecified"))
    )
    (net (code "48") (name "D55") (class "Default")
      (node (ref "CN4") (pin "19") (pinfunction "19_19") (pintype "unspecified"))
      (node (ref "H3") (pin "10") (pinfunction "10_10") (pintype "input"))
      (node (ref "H6") (pin "19") (pinfunction "19_19") (pintype "input"))
      (node (ref "J5") (pin "10") (pinfunction "10_10") (pintype "unspecified"))
      (node (ref "J7") (pin "9") (pinfunction "9_9") (pintype "input"))
      (node (ref "P1") (pin "31") (pinfunction "31_31") (pintype "unspecified"))
      (node (ref "U1") (pin "19") (pinfunction "19_19") (pintype "unspecified"))
    )
    (net (code "49") (name "D56") (class "Default")
      (node (ref "CN4") (pin "21") (pinfunction "21_21") (pintype "unspecified"))
      (node (ref "H3") (pin "14") (pinfunction "14_14") (pintype "input"))
      (node (ref "H6") (pin "21") (pinfunction "21_21") (pintype "input"))
      (node (ref "J5") (pin "11") (pinfunction "11_11") (pintype "unspecified"))
      (node (ref "J7") (pin "13") (pinfunction "13_13") (pintype "input"))
      (node (ref "P1") (pin "30") (pinfunction "30_30") (pintype "unspecified"))
      (node (ref "U1") (pin "21") (pinfunction "21_21") (pintype "unspecified"))
    )
    (net (code "50") (name "D57") (class "Default")
      (node (ref "CN4") (pin "23") (pinfunction "23_23") (pintype "unspecified"))
      (node (ref "H3") (pin "16") (pinfunction "16_16") (pintype "input"))
      (node (ref "H6") (pin "23") (pinfunction "23_23") (pintype "input"))
      (node (ref "J5") (pin "12") (pinfunction "12_12") (pintype "unspecified"))
      (node (ref "J7") (pin "15") (pinfunction "15_15") (pintype "input"))
      (node (ref "P1") (pin "29") (pinfunction "29_29") (pintype "unspecified"))
      (node (ref "U1") (pin "23") (pinfunction "23_23") (pintype "unspecified"))
    )
    (net (code "51") (name "D71") (class "Default")
      (node (ref "H3") (pin "15") (pinfunction "15_15") (pintype "input"))
      (node (ref "H6") (pin "39") (pinfunction "39_39") (pintype "input"))
      (node (ref "J5") (pin "20") (pinfunction "20_20") (pintype "unspecified"))
      (node (ref "J7") (pin "16") (pinfunction "16_16") (pintype "input"))
      (node (ref "P1") (pin "21") (pinfunction "21_21") (pintype "unspecified"))
    )
    (net (code "52") (name "D72") (class "Default")
      (node (ref "H3") (pin "13") (pinfunction "13_13") (pintype "input"))
      (node (ref "H6") (pin "37") (pinfunction "37_37") (pintype "input"))
      (node (ref "J5") (pin "19") (pinfunction "19_19") (pintype "unspecified"))
      (node (ref "J7") (pin "14") (pinfunction "14_14") (pintype "input"))
      (node (ref "P1") (pin "22") (pinfunction "22_22") (pintype "unspecified"))
    )
    (net (code "53") (name "GND") (class "Default")
      (node (ref "C18") (pin "1") (pinfunction "1_1") (pintype "unspecified"))
      (node (ref "CARD1") (pin "6") (pinfunction "VSS_6") (pintype "unspecified"))
      (node (ref "D2") (pin "1") (pinfunction "1_1") (pintype "unspecified"))
      (node (ref "D2") (pin "2") (pinfunction "2_2") (pintype "unspecified"))
      (node (ref "D6") (pin "2") (pinfunction "2_2") (pintype "unspecified"))
      (node (ref "D7") (pin "2") (pinfunction "2_2") (pintype "unspecified"))
      (node (ref "H1") (pin "8") (pinfunction "8_8") (pintype "input"))
      (node (ref "H2") (pin "11") (pinfunction "11_11") (pintype "input"))
      (node (ref "H2") (pin "13") (pinfunction "13_13") (pintype "input"))
      (node (ref "H3") (pin "12") (pinfunction "12_12") (pintype "input"))
      (node (ref "H4") (pin "17") (pinfunction "17_17") (pintype "input"))
      (node (ref "H4") (pin "22") (pinfunction "22_22") (pintype "input"))
      (node (ref "H4") (pin "27") (pinfunction "27_27") (pintype "input"))
      (node (ref "H4") (pin "5") (pinfunction "5_5") (pintype "input"))
      (node (ref "H5") (pin "1") (pinfunction "1_1") (pintype "unspecified"))
      (node (ref "H5") (pin "2") (pinfunction "2_2") (pintype "unspecified"))
      (node (ref "H5") (pin "3") (pinfunction "3_3") (pintype "unspecified"))
      (node (ref "J1") (pin "7") (pinfunction "7_7") (pintype "unspecified"))
      (node (ref "J11") (pin "18") (pinfunction "18_18") (pintype "input"))
      (node (ref "J11") (pin "21") (pinfunction "21_21") (pintype "input"))
      (node (ref "J11") (pin "28") (pinfunction "28_28") (pintype "input"))
      (node (ref "J11") (pin "6") (pinfunction "6_6") (pintype "input"))
      (node (ref "J13") (pin "1") (pinfunction "1_1") (pintype "unspecified"))
      (node (ref "J13") (pin "10") (pinfunction "10_10") (pintype "unspecified"))
      (node (ref "J13") (pin "11") (pinfunction "11_11") (pintype "unspecified"))
      (node (ref "J13") (pin "12") (pinfunction "12_12") (pintype "unspecified"))
      (node (ref "J13") (pin "13") (pinfunction "13_13") (pintype "unspecified"))
      (node (ref "J13") (pin "14") (pinfunction "14_14") (pintype "unspecified"))
      (node (ref "J13") (pin "15") (pinfunction "15_15") (pintype "unspecified"))
      (node (ref "J13") (pin "16") (pinfunction "16_16") (pintype "unspecified"))
      (node (ref "J13") (pin "17") (pinfunction "17_17") (pintype "unspecified"))
      (node (ref "J13") (pin "18") (pinfunction "18_18") (pintype "unspecified"))
      (node (ref "J13") (pin "19") (pinfunction "19_19") (pintype "unspecified"))
      (node (ref "J13") (pin "2") (pinfunction "2_2") (pintype "unspecified"))
      (node (ref "J13") (pin "20") (pinfunction "20_20") (pintype "unspecified"))
      (node (ref "J13") (pin "3") (pinfunction "3_3") (pintype "unspecified"))
      (node (ref "J13") (pin "4") (pinfunction "4_4") (pintype "unspecified"))
      (node (ref "J13") (pin "5") (pinfunction "5_5") (pintype "unspecified"))
      (node (ref "J13") (pin "6") (pinfunction "6_6") (pintype "unspecified"))
      (node (ref "J13") (pin "7") (pinfunction "7_7") (pintype "unspecified"))
      (node (ref "J13") (pin "8") (pinfunction "8_8") (pintype "unspecified"))
      (node (ref "J13") (pin "9") (pinfunction "9_9") (pintype "unspecified"))
      (node (ref "J3") (pin "12") (pinfunction "12_12") (pintype "input"))
      (node (ref "J3") (pin "14") (pinfunction "14_14") (pintype "input"))
      (node (ref "J4") (pin "1") (pinfunction "1_1") (pintype "unspecified"))
      (node (ref "J4") (pin "10") (pinfunction "10_10") (pintype "unspecified"))
      (node (ref "J4") (pin "11") (pinfunction "11_11") (pintype "unspecified"))
      (node (ref "J4") (pin "12") (pinfunction "12_12") (pintype "unspecified"))
      (node (ref "J4") (pin "13") (pinfunction "13_13") (pintype "unspecified"))
      (node (ref "J4") (pin "14") (pinfunction "14_14") (pintype "unspecified"))
      (node (ref "J4") (pin "15") (pinfunction "15_15") (pintype "unspecified"))
      (node (ref "J4") (pin "16") (pinfunction "16_16") (pintype "unspecified"))
      (node (ref "J4") (pin "17") (pinfunction "17_17") (pintype "unspecified"))
      (node (ref "J4") (pin "18") (pinfunction "18_18") (pintype "unspecified"))
      (node (ref "J4") (pin "19") (pinfunction "19_19") (pintype "unspecified"))
      (node (ref "J4") (pin "2") (pinfunction "2_2") (pintype "unspecified"))
      (node (ref "J4") (pin "20") (pinfunction "20_20") (pintype "unspecified"))
      (node (ref "J4") (pin "3") (pinfunction "3_3") (pintype "unspecified"))
      (node (ref "J4") (pin "4") (pinfunction "4_4") (pintype "unspecified"))
      (node (ref "J4") (pin "5") (pinfunction "5_5") (pintype "unspecified"))
      (node (ref "J4") (pin "6") (pinfunction "6_6") (pintype "unspecified"))
      (node (ref "J4") (pin "7") (pinfunction "7_7") (pintype "unspecified"))
      (node (ref "J4") (pin "8") (pinfunction "8_8") (pintype "unspecified"))
      (node (ref "J4") (pin "9") (pinfunction "9_9") (pintype "unspecified"))
      (node (ref "J7") (pin "11") (pinfunction "11_11") (pintype "input"))
      (node (ref "J9") (pin "1") (pinfunction "1_1") (pintype "unspecified"))
      (node (ref "J9") (pin "2") (pinfunction "2_2") (pintype "unspecified"))
      (node (ref "J9") (pin "3") (pinfunction "3_3") (pintype "unspecified"))
      (node (ref "NRST") (pin "1") (pinfunction "1_1") (pintype "unspecified"))
      (node (ref "NRST") (pin "2") (pinfunction "2_2") (pintype "unspecified"))
    )
    (net (code "54") (name "IOREF") (class "Default")
      (node (ref "H2") (pin "3") (pinfunction "3_3") (pintype "input"))
      (node (ref "J3") (pin "4") (pinfunction "4_4") (pintype "input"))
    )
    (net (code "55") (name "MISO") (class "Default")
      (node (ref "CN2") (pin "3") (pinfunction "3_3") (pintype "unspecified"))
      (node (ref "CN4") (pin "3") (pinfunction "3_3") (pintype "unspecified"))
      (node (ref "H1") (pin "12") (pinfunction "12_12") (pintype "input"))
      (node (ref "H6") (pin "3") (pinfunction "3_3") (pintype "input"))
      (node (ref "J1") (pin "11") (pinfunction "11_11") (pintype "unspecified"))
      (node (ref "J5") (pin "2") (pinfunction "2_2") (pintype "unspecified"))
      (node (ref "P1") (pin "39") (pinfunction "39_39") (pintype "unspecified"))
      (node (ref "U1") (pin "3") (pinfunction "3_3") (pintype "unspecified"))
    )
    (net (code "56") (name "MISO2") (class "Default")
      (node (ref "CN4") (pin "20") (pinfunction "20_20") (pintype "unspecified"))
      (node (ref "H1") (pin "19") (pinfunction "19_19") (pintype "input"))
      (node (ref "H6") (pin "20") (pinfunction "20_20") (pintype "input"))
      (node (ref "J1") (pin "20") (pinfunction "20_20") (pintype "unspecified"))
      (node (ref "J10") (pin "10") (pinfunction "10_10") (pintype "unspecified"))
      (node (ref "P1") (pin "11") (pinfunction "11_11") (pintype "unspecified"))
      (node (ref "U1") (pin "20") (pinfunction "20_20") (pintype "unspecified"))
    )
    (net (code "57") (name "MOSI") (class "Default")
      (node (ref "CN2") (pin "5") (pinfunction "5_5") (pintype "unspecified"))
      (node (ref "CN4") (pin "5") (pinfunction "5_5") (pintype "unspecified"))
      (node (ref "H1") (pin "14") (pinfunction "14_14") (pintype "input"))
      (node (ref "H6") (pin "5") (pinfunction "5_5") (pintype "input"))
      (node (ref "J1") (pin "13") (pinfunction "13_13") (pintype "unspecified"))
      (node (ref "J5") (pin "3") (pinfunction "3_3") (pintype "unspecified"))
      (node (ref "P1") (pin "38") (pinfunction "38_38") (pintype "unspecified"))
      (node (ref "U1") (pin "5") (pinfunction "5_5") (pintype "unspecified"))
    )
    (net (code "58") (name "MOSI2") (class "Default")
      (node (ref "CN2") (pin "14") (pinfunction "14_14") (pintype "unspecified"))
      (node (ref "CN4") (pin "14") (pinfunction "14_14") (pintype "unspecified"))
      (node (ref "H1") (pin "13") (pinfunction "13_13") (pintype "input"))
      (node (ref "H6") (pin "14") (pinfunction "14_14") (pintype "input"))
      (node (ref "J1") (pin "14") (pinfunction "14_14") (pintype "unspecified"))
      (node (ref "J10") (pin "7") (pinfunction "7_7") (pintype "unspecified"))
      (node (ref "P1") (pin "14") (pinfunction "14_14") (pintype "unspecified"))
      (node (ref "U1") (pin "14") (pinfunction "14_14") (pintype "unspecified"))
    )
    (net (code "59") (name "NRST") (class "Default")
      (node (ref "H2") (pin "5") (pinfunction "5_5") (pintype "input"))
      (node (ref "J3") (pin "6") (pinfunction "6_6") (pintype "input"))
      (node (ref "NRST") (pin "3") (pinfunction "3_3") (pintype "unspecified"))
      (node (ref "NRST") (pin "4") (pinfunction "4_4") (pintype "unspecified"))
    )
    (net (code "60") (name "NSS") (class "Default")
      (node (ref "H1") (pin "9") (pinfunction "9_9") (pintype "input"))
      (node (ref "J1") (pin "10") (pinfunction "10_10") (pintype "unspecified"))
    )
    (net (code "61") (name "NSS2") (class "Default")
      (node (ref "CN4") (pin "18") (pinfunction "18_18") (pintype "unspecified"))
      (node (ref "H1") (pin "17") (pinfunction "17_17") (pintype "input"))
      (node (ref "H6") (pin "18") (pinfunction "18_18") (pintype "input"))
      (node (ref "J1") (pin "18") (pinfunction "18_18") (pintype "unspecified"))
      (node (ref "J10") (pin "9") (pinfunction "9_9") (pintype "unspecified"))
      (node (ref "P1") (pin "12") (pinfunction "12_12") (pintype "unspecified"))
      (node (ref "U1") (pin "18") (pinfunction "18_18") (pintype "unspecified"))
    )
    (net (code "62") (name "Net-(D6-Pad1)") (class "Default")
      (node (ref "D6") (pin "1") (pinfunction "1_1") (pintype "unspecified"))
      (node (ref "R1") (pin "1") (pinfunction "1_1") (pintype "unspecified"))
    )
    (net (code "63") (name "Net-(D7-Pad1)") (class "Default")
      (node (ref "D7") (pin "1") (pinfunction "1_1") (pintype "unspecified"))
      (node (ref "R2") (pin "1") (pinfunction "1_1") (pintype "unspecified"))
    )
    (net (code "64") (name "Net-(J2-Pad1)") (class "Default")
      (node (ref "J2") (pin "1") (pinfunction "1_1") (pintype "unspecified"))
      (node (ref "R24") (pin "2") (pinfunction "2_2") (pintype "unspecified"))
    )
    (net (code "65") (name "QCLK") (class "Default")
      (node (ref "H4") (pin "15") (pinfunction "15_15") (pintype "input"))
      (node (ref "J11") (pin "16") (pinfunction "16_16") (pintype "input"))
    )
    (net (code "66") (name "QCS") (class "Default")
      (node (ref "H4") (pin "13") (pinfunction "13_13") (pintype "input"))
      (node (ref "J11") (pin "14") (pinfunction "14_14") (pintype "input"))
    )
    (net (code "67") (name "QD0") (class "Default")
      (node (ref "H4") (pin "23") (pinfunction "23_23") (pintype "input"))
      (node (ref "J11") (pin "24") (pinfunction "24_24") (pintype "input"))
    )
    (net (code "68") (name "QD1") (class "Default")
      (node (ref "H4") (pin "21") (pinfunction "21_21") (pintype "input"))
      (node (ref "J11") (pin "22") (pinfunction "22_22") (pintype "input"))
    )
    (net (code "69") (name "QD2") (class "Default")
      (node (ref "H4") (pin "25") (pinfunction "25_25") (pintype "input"))
      (node (ref "J11") (pin "26") (pinfunction "26_26") (pintype "input"))
    )
    (net (code "70") (name "QD3") (class "Default")
      (node (ref "H4") (pin "19") (pinfunction "19_19") (pintype "input"))
      (node (ref "J11") (pin "20") (pinfunction "20_20") (pintype "input"))
    )
    (net (code "71") (name "SCK") (class "Default")
      (node (ref "CN2") (pin "1") (pinfunction "1_1") (pintype "unspecified"))
      (node (ref "CN4") (pin "1") (pinfunction "1_1") (pintype "unspecified"))
      (node (ref "H1") (pin "10") (pinfunction "10_10") (pintype "input"))
      (node (ref "H6") (pin "1") (pinfunction "1_1") (pintype "input"))
      (node (ref "J1") (pin "9") (pinfunction "9_9") (pintype "unspecified"))
      (node (ref "J5") (pin "1") (pinfunction "1_1") (pintype "unspecified"))
      (node (ref "P1") (pin "40") (pinfunction "40_40") (pintype "unspecified"))
      (node (ref "U1") (pin "1") (pinfunction "1_1") (pintype "unspecified"))
    )
    (net (code "72") (name "SCK2") (class "Default")
      (node (ref "CN2") (pin "16") (pinfunction "16_16") (pintype "unspecified"))
      (node (ref "CN4") (pin "16") (pinfunction "16_16") (pintype "unspecified"))
      (node (ref "H1") (pin "15") (pinfunction "15_15") (pintype "input"))
      (node (ref "H6") (pin "16") (pinfunction "16_16") (pintype "input"))
      (node (ref "J1") (pin "16") (pinfunction "16_16") (pintype "unspecified"))
      (node (ref "J10") (pin "8") (pinfunction "8_8") (pintype "unspecified"))
      (node (ref "P1") (pin "13") (pinfunction "13_13") (pintype "unspecified"))
      (node (ref "U1") (pin "16") (pinfunction "16_16") (pintype "unspecified"))
    )
    (net (code "73") (name "SCL") (class "Default")
      (node (ref "CN2") (pin "2") (pinfunction "2_2") (pintype "unspecified"))
      (node (ref "CN4") (pin "2") (pinfunction "2_2") (pintype "unspecified"))
      (node (ref "H1") (pin "2") (pinfunction "2_2") (pintype "input"))
      (node (ref "H6") (pin "2") (pinfunction "2_2") (pintype "input"))
      (node (ref "J1") (pin "1") (pinfunction "1_1") (pintype "unspecified"))
      (node (ref "J10") (pin "1") (pinfunction "1_1") (pintype "unspecified"))
      (node (ref "P1") (pin "20") (pinfunction "20_20") (pintype "unspecified"))
      (node (ref "U1") (pin "2") (pinfunction "2_2") (pintype "unspecified"))
    )
    (net (code "74") (name "SDA") (class "Default")
      (node (ref "CN2") (pin "4") (pinfunction "4_4") (pintype "unspecified"))
      (node (ref "CN4") (pin "4") (pinfunction "4_4") (pintype "unspecified"))
      (node (ref "H1") (pin "4") (pinfunction "4_4") (pintype "input"))
      (node (ref "H6") (pin "4") (pinfunction "4_4") (pintype "input"))
      (node (ref "J1") (pin "3") (pinfunction "3_3") (pintype "unspecified"))
      (node (ref "J10") (pin "2") (pinfunction "2_2") (pintype "unspecified"))
      (node (ref "P1") (pin "19") (pinfunction "19_19") (pintype "unspecified"))
      (node (ref "U1") (pin "4") (pinfunction "4_4") (pintype "unspecified"))
    )
    (net (code "75") (name "URX") (class "Default")
      (node (ref "H4") (pin "16") (pinfunction "16_16") (pintype "input"))
      (node (ref "J11") (pin "15") (pinfunction "15_15") (pintype "input"))
    )
    (net (code "76") (name "UTX") (class "Default")
      (node (ref "H4") (pin "14") (pinfunction "14_14") (pintype "input"))
      (node (ref "J11") (pin "13") (pinfunction "13_13") (pintype "input"))
    )
    (net (code "77") (name "VIN") (class "Default")
      (node (ref "H2") (pin "15") (pinfunction "15_15") (pintype "input"))
      (node (ref "J3") (pin "16") (pinfunction "16_16") (pintype "input"))
    )
    (net (code "78") (name "unconnected-(CARD1-SHELL-Pad11)") (class "Default")
      (node (ref "CARD1") (pin "11") (pinfunction "SHELL_11") (pintype "unspecified+no_connect"))
    )
    (net (code "79") (name "unconnected-(CARD1-SW_CONTACT-Pad9)") (class "Default")
      (node (ref "CARD1") (pin "9") (pinfunction "SW_CONTACT_9") (pintype "unspecified+no_connect"))
    )
    (net (code "80") (name "unconnected-(CARD1-SW_SPRING-Pad10)") (class "Default")
      (node (ref "CARD1") (pin "10") (pinfunction "SW_SPRING_10") (pintype "unspecified+no_connect"))
    )
    (net (code "81") (name "unconnected-(CN2-Pad17)") (class "Default")
      (node (ref "CN2") (pin "17") (pinfunction "17_17") (pintype "unspecified"))
    )
    (net (code "82") (name "unconnected-(CN2-Pad18)") (class "Default")
      (node (ref "CN2") (pin "18") (pinfunction "18_18") (pintype "unspecified"))
    )
    (net (code "83") (name "unconnected-(CN2-Pad19)") (class "Default")
      (node (ref "CN2") (pin "19") (pinfunction "19_19") (pintype "unspecified"))
    )
    (net (code "84") (name "unconnected-(CN2-Pad20)") (class "Default")
      (node (ref "CN2") (pin "20") (pinfunction "20_20") (pintype "unspecified"))
    )
    (net (code "85") (name "unconnected-(CN4-Pad31)") (class "Default")
      (node (ref "CN4") (pin "31") (pinfunction "31_31") (pintype "unspecified"))
    )
    (net (code "86") (name "unconnected-(CN4-Pad32)") (class "Default")
      (node (ref "CN4") (pin "32") (pinfunction "32_32") (pintype "unspecified"))
    )
    (net (code "87") (name "unconnected-(CN4-Pad33)") (class "Default")
      (node (ref "CN4") (pin "33") (pinfunction "33_33") (pintype "unspecified"))
    )
    (net (code "88") (name "unconnected-(CN4-Pad34)") (class "Default")
      (node (ref "CN4") (pin "34") (pinfunction "34_34") (pintype "unspecified"))
    )
    (net (code "89") (name "unconnected-(H2-Pad1)") (class "Default")
      (node (ref "H2") (pin "1") (pinfunction "1_1") (pintype "input"))
    )
    (net (code "90") (name "unconnected-(J3-Pad2)") (class "Default")
      (node (ref "J3") (pin "2") (pinfunction "2_2") (pintype "input"))
    )
    (net (code "91") (name "unconnected-(P1-Pad41)") (class "Default")
      (node (ref "P1") (pin "41") (pinfunction "41_41") (pintype "unspecified"))
    )
    (net (code "92") (name "unconnected-(P1-Pad42)") (class "Default")
      (node (ref "P1") (pin "42") (pinfunction "42_42") (pintype "unspecified"))
    )
    (net (code "93") (name "unconnected-(U1-Pad25)") (class "Default")
      (node (ref "U1") (pin "25") (pinfunction "25_25") (pintype "unspecified"))
    )
    (net (code "94") (name "unconnected-(U1-Pad26)") (class "Default")
      (node (ref "U1") (pin "26") (pinfunction "26_26") (pintype "unspecified"))
    )
    (net (code "95") (name "unconnected-(U1-Pad27)") (class "Default")
      (node (ref "U1") (pin "27") (pinfunction "27_27") (pintype "unspecified"))
    )
    (net (code "96") (name "unconnected-(U1-Pad28)") (class "Default")
      (node (ref "U1") (pin "28") (pinfunction "28_28") (pintype "unspecified"))
    )
  )
)
